# 01-eagleClass-555.net
KiCad netlist of a schematic drawn in EAGLE
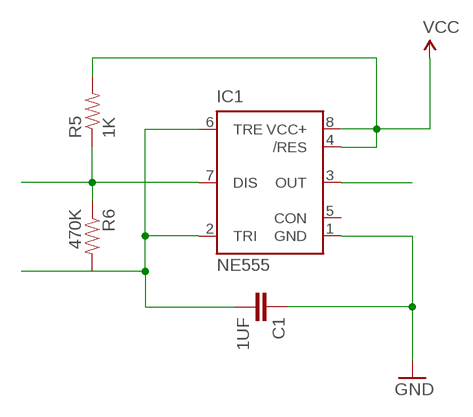
[diagram p0: schematic, sheet 1]

(export (version "E")
  (design (tool "Eeschema 10.0.6"))
  (components
    (comp (ref "C1")
      (value "1UF")
      (footprint "eagle-import:AXIAL-5MM")
      (libsource (lib "eagle-import") (part "CAP_"))
    )
    (comp (ref "IC1")
      (value "NE555")
      (footprint "eagle-import:DIL-08")
      (fields (field (name "MF") "Arrow Electronics") (field (name "MPN") "NE555N"))
      (libsource (lib "eagle-import") (part "NE555"))
    )
    (comp (ref "R5")
      (value "1K")
      (footprint "eagle-import:AXIAL-0.3EZ")
      (fields (field (name "PROD_ID") "1.0KQBK-ND"))
      (libsource (lib "eagle-import") (part "1KOHM-1/4W-5%(PTH)HORIZ-KIT"))
    )
    (comp (ref "R6")
      (value "470K")
      (footprint "eagle-import:AXIAL-0.3EZ")
      (libsource (lib "eagle-import") (part "1KOHM-1/4W-5%(PTH)HORIZ-KIT"))
    )
  )
  (nets
    (net (code "1") (name "GND") (class "Default")
      (node (ref "C1") (pin "P$1") (pinfunction "1_P$1") (pintype "passive"))
      (node (ref "IC1") (pin "1") (pinfunction "GND_1") (pintype "power_in"))
    )
    (net (code "2") (name "Net-(C1-2)") (class "Default")
      (node (ref "C1") (pin "P$2") (pinfunction "2_P$2") (pintype "passive"))
      (node (ref "IC1") (pin "2") (pinfunction "TRI_2") (pintype "input"))
      (node (ref "IC1") (pin "6") (pinfunction "TRE_6") (pintype "input"))
      (node (ref "R6") (pin "P$2") (pinfunction "2_P$2") (pintype "passive"))
    )
    (net (code "3") (name "Net-(IC1-DIS)") (class "Default")
      (node (ref "IC1") (pin "7") (pinfunction "DIS_7") (pintype "input"))
      (node (ref "R5") (pin "P$1") (pinfunction "1_P$1") (pintype "passive"))
      (node (ref "R6") (pin "P$1") (pinfunction "1_P$1") (pintype "passive"))
    )
    (net (code "4") (name "VCC") (class "Default")
      (node (ref "IC1") (pin "4") (pinfunction "/RES_4") (pintype "input"))
      (node (ref "IC1") (pin "8") (pinfunction "VCC+_8") (pintype "power_in"))
      (node (ref "R5") (pin "P$2") (pinfunction "2_P$2") (pintype "passive"))
    )
    (net (code "5") (name "unconnected-(IC1-CON-Pad5)") (class "Default")
      (node (ref "IC1") (pin "5") (pinfunction "CON_5") (pintype "input"))
    )
    (net (code "6") (name "unconnected-(IC1-OUT-Pad3)") (class "Default")
      (node (ref "IC1") (pin "3") (pinfunction "OUT_3") (pintype "output"))
    )
  )
)
